# PCB_Telemetria_2020.net
KiCad netlist of a schematic drawn in EAGLE
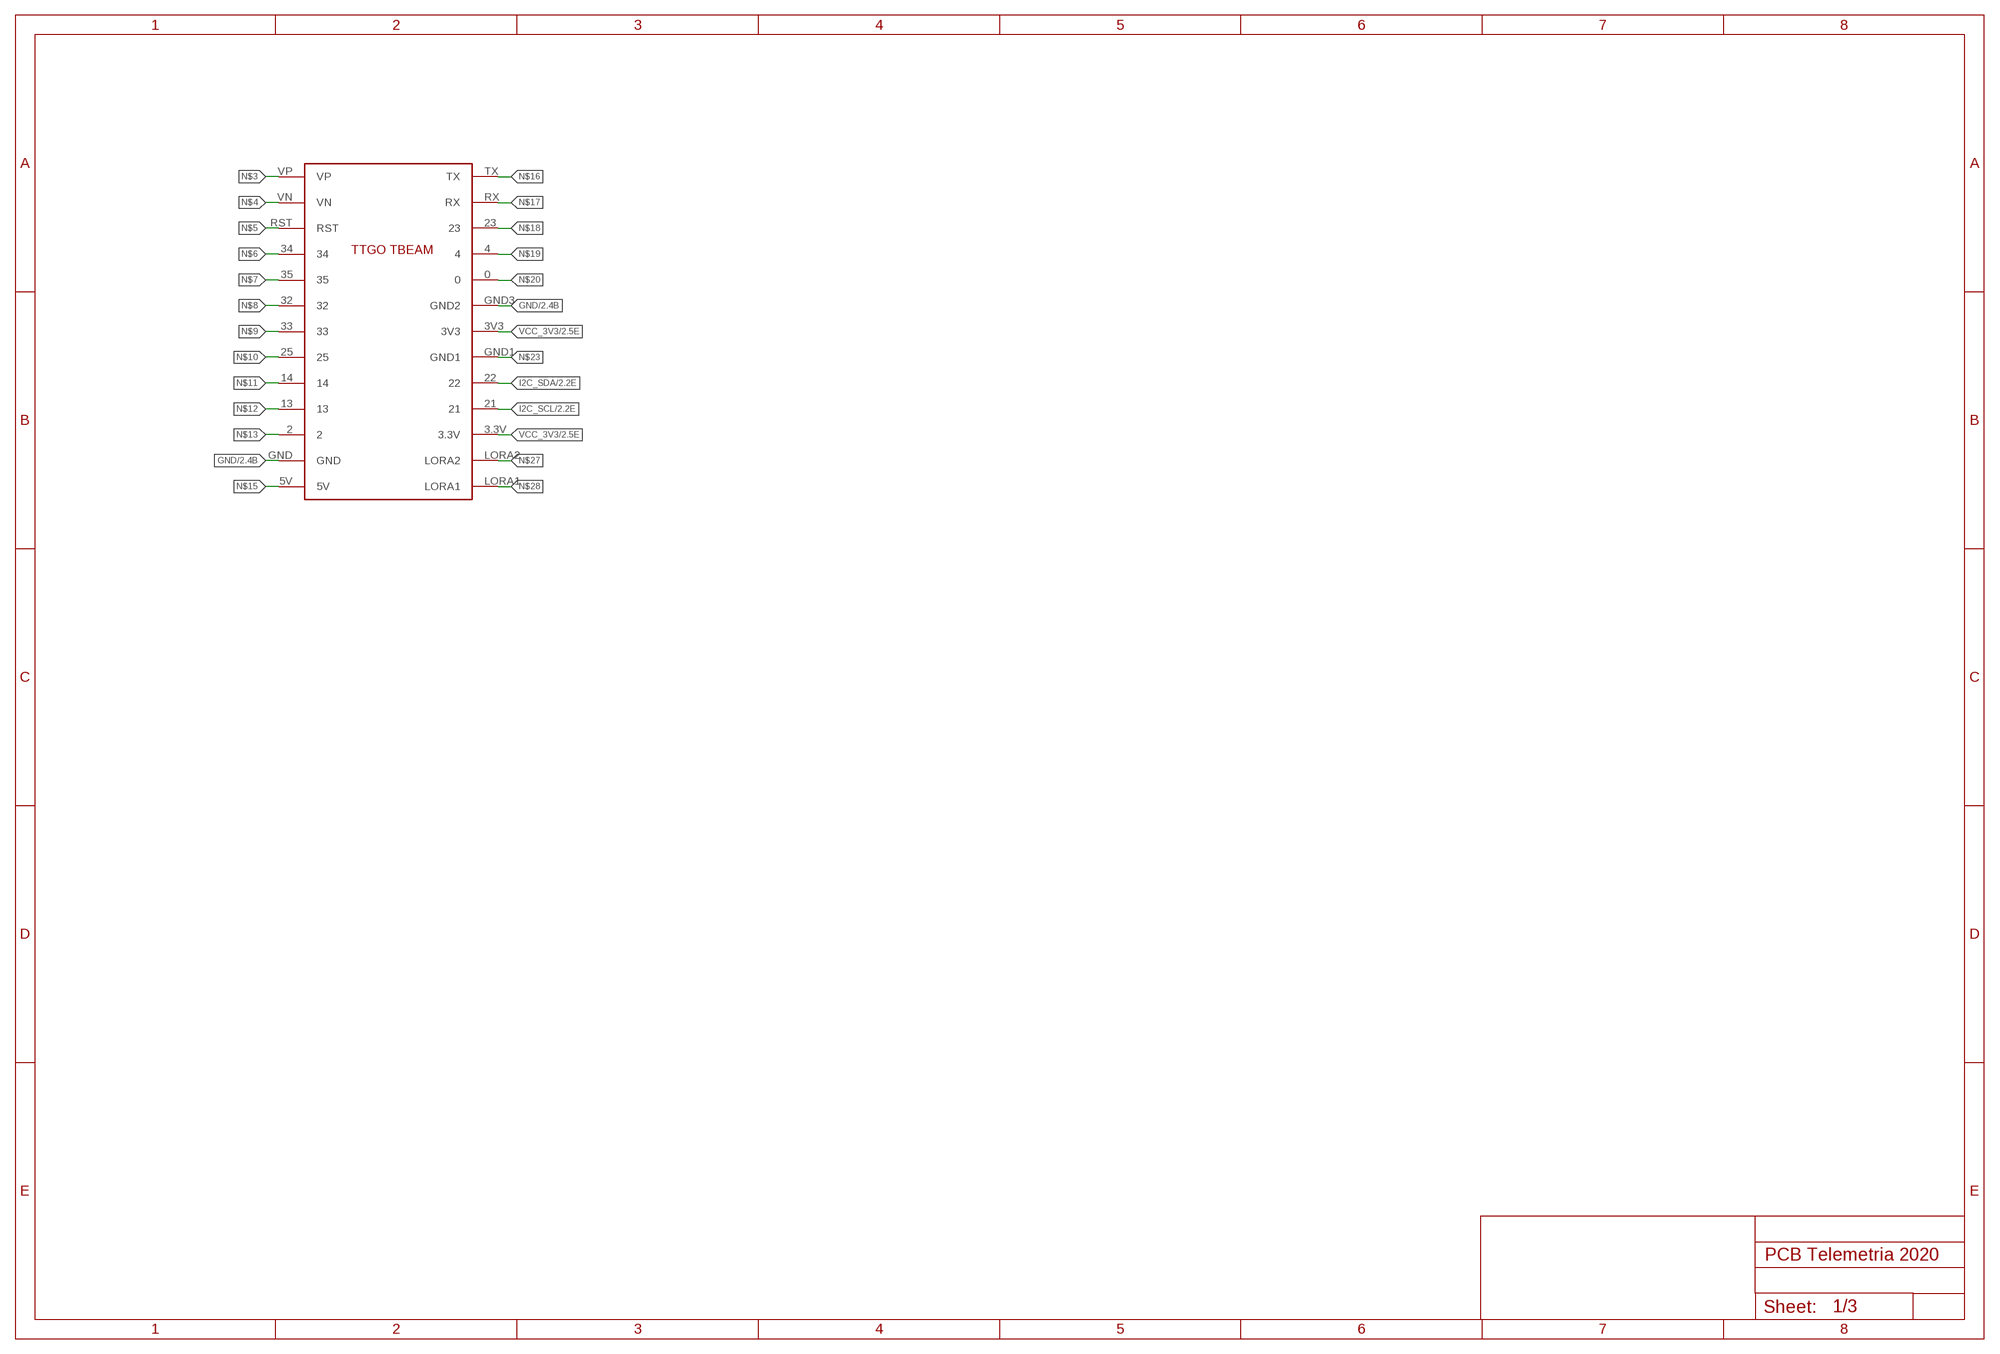
[diagram p0: schematic, sheet 1]
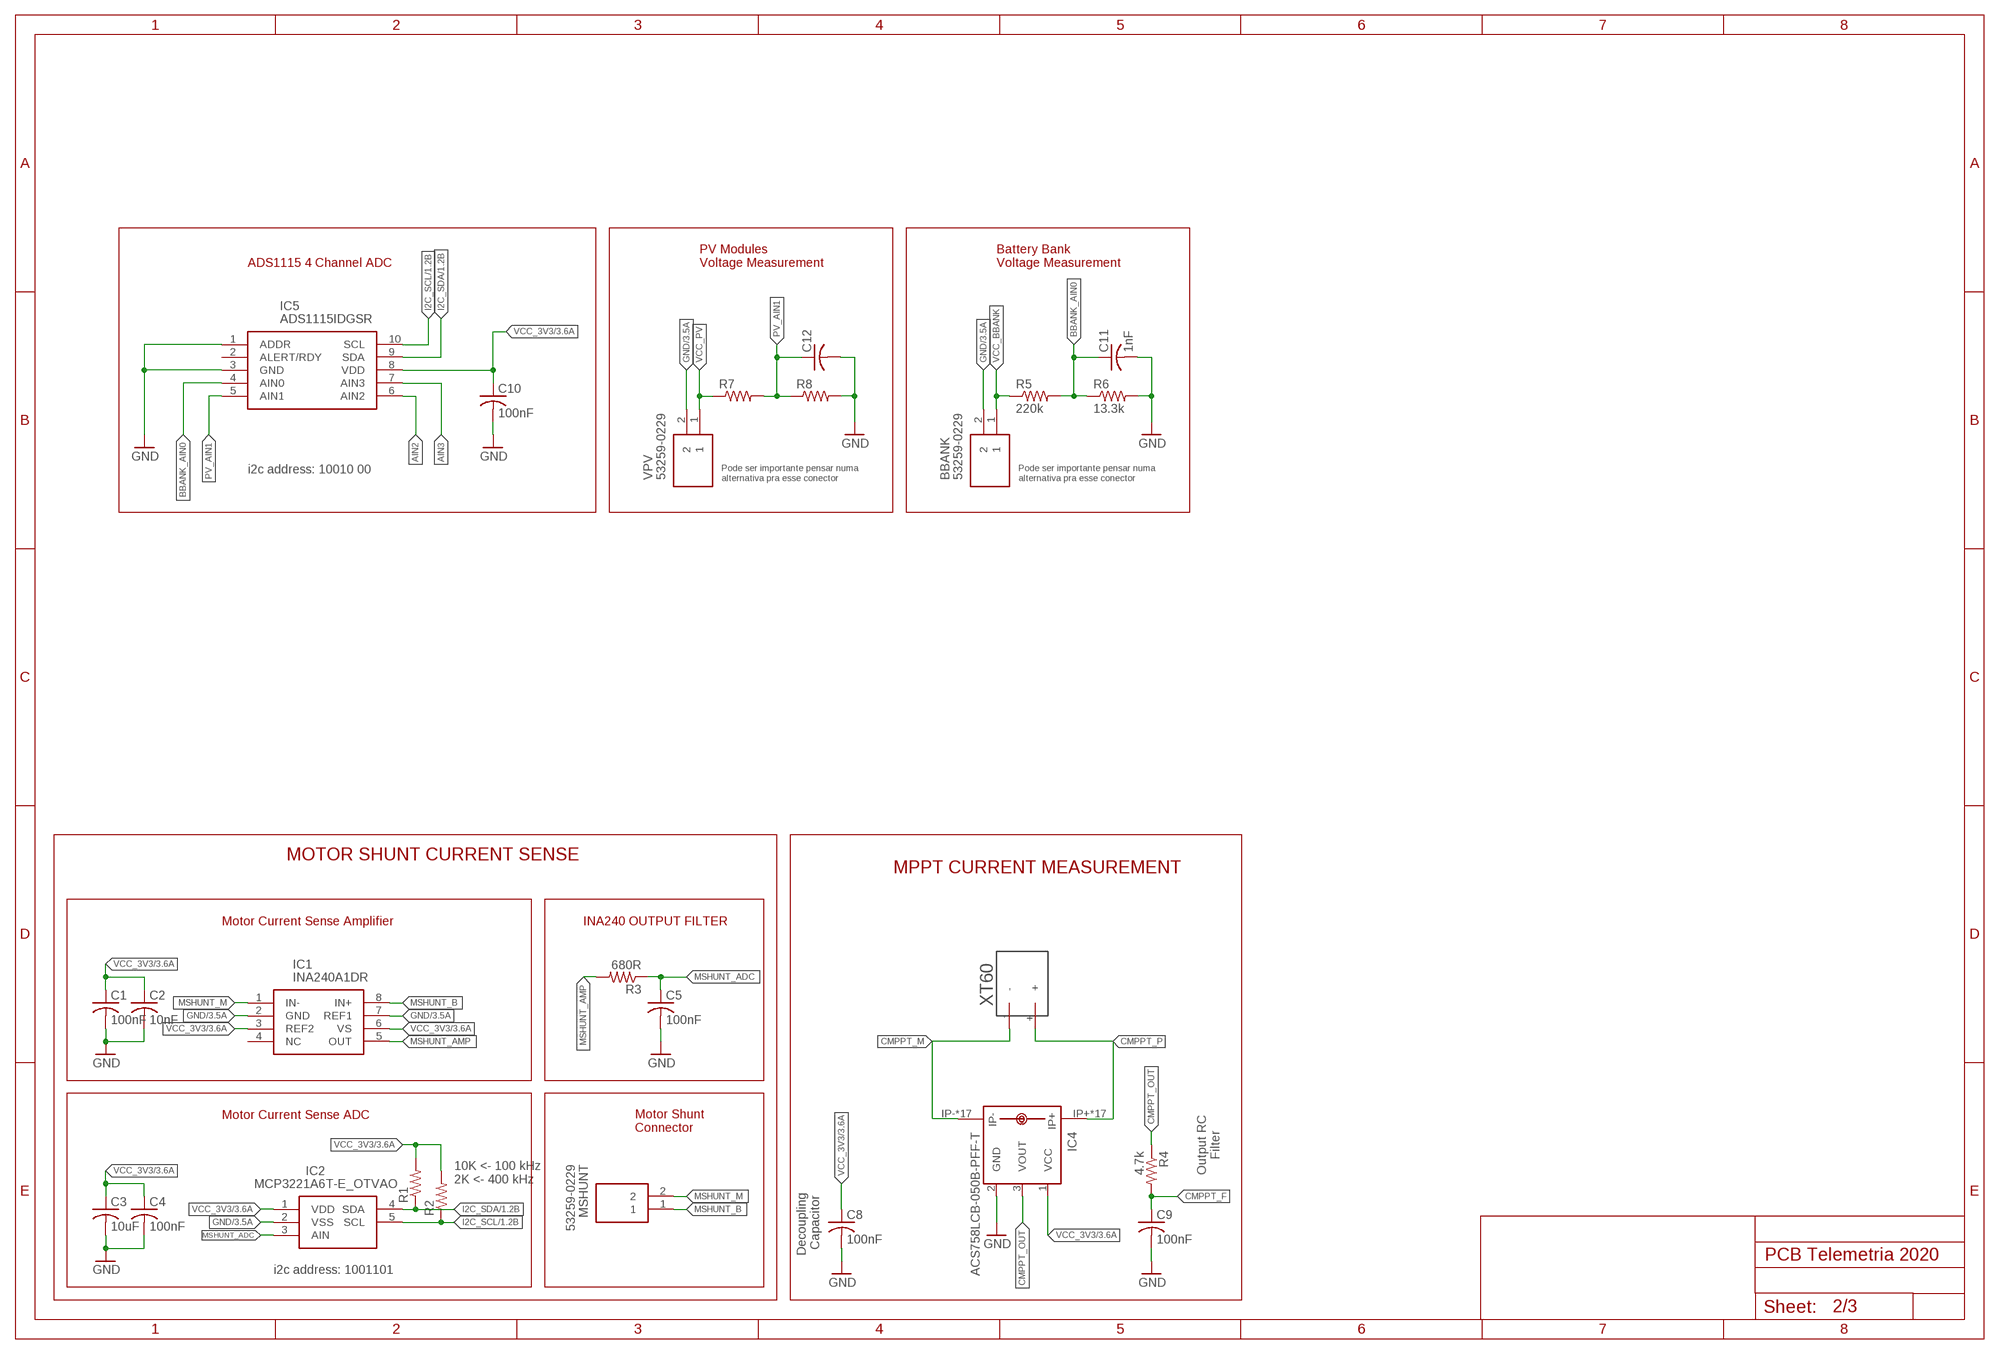
[diagram p1: schematic, sheet 2]
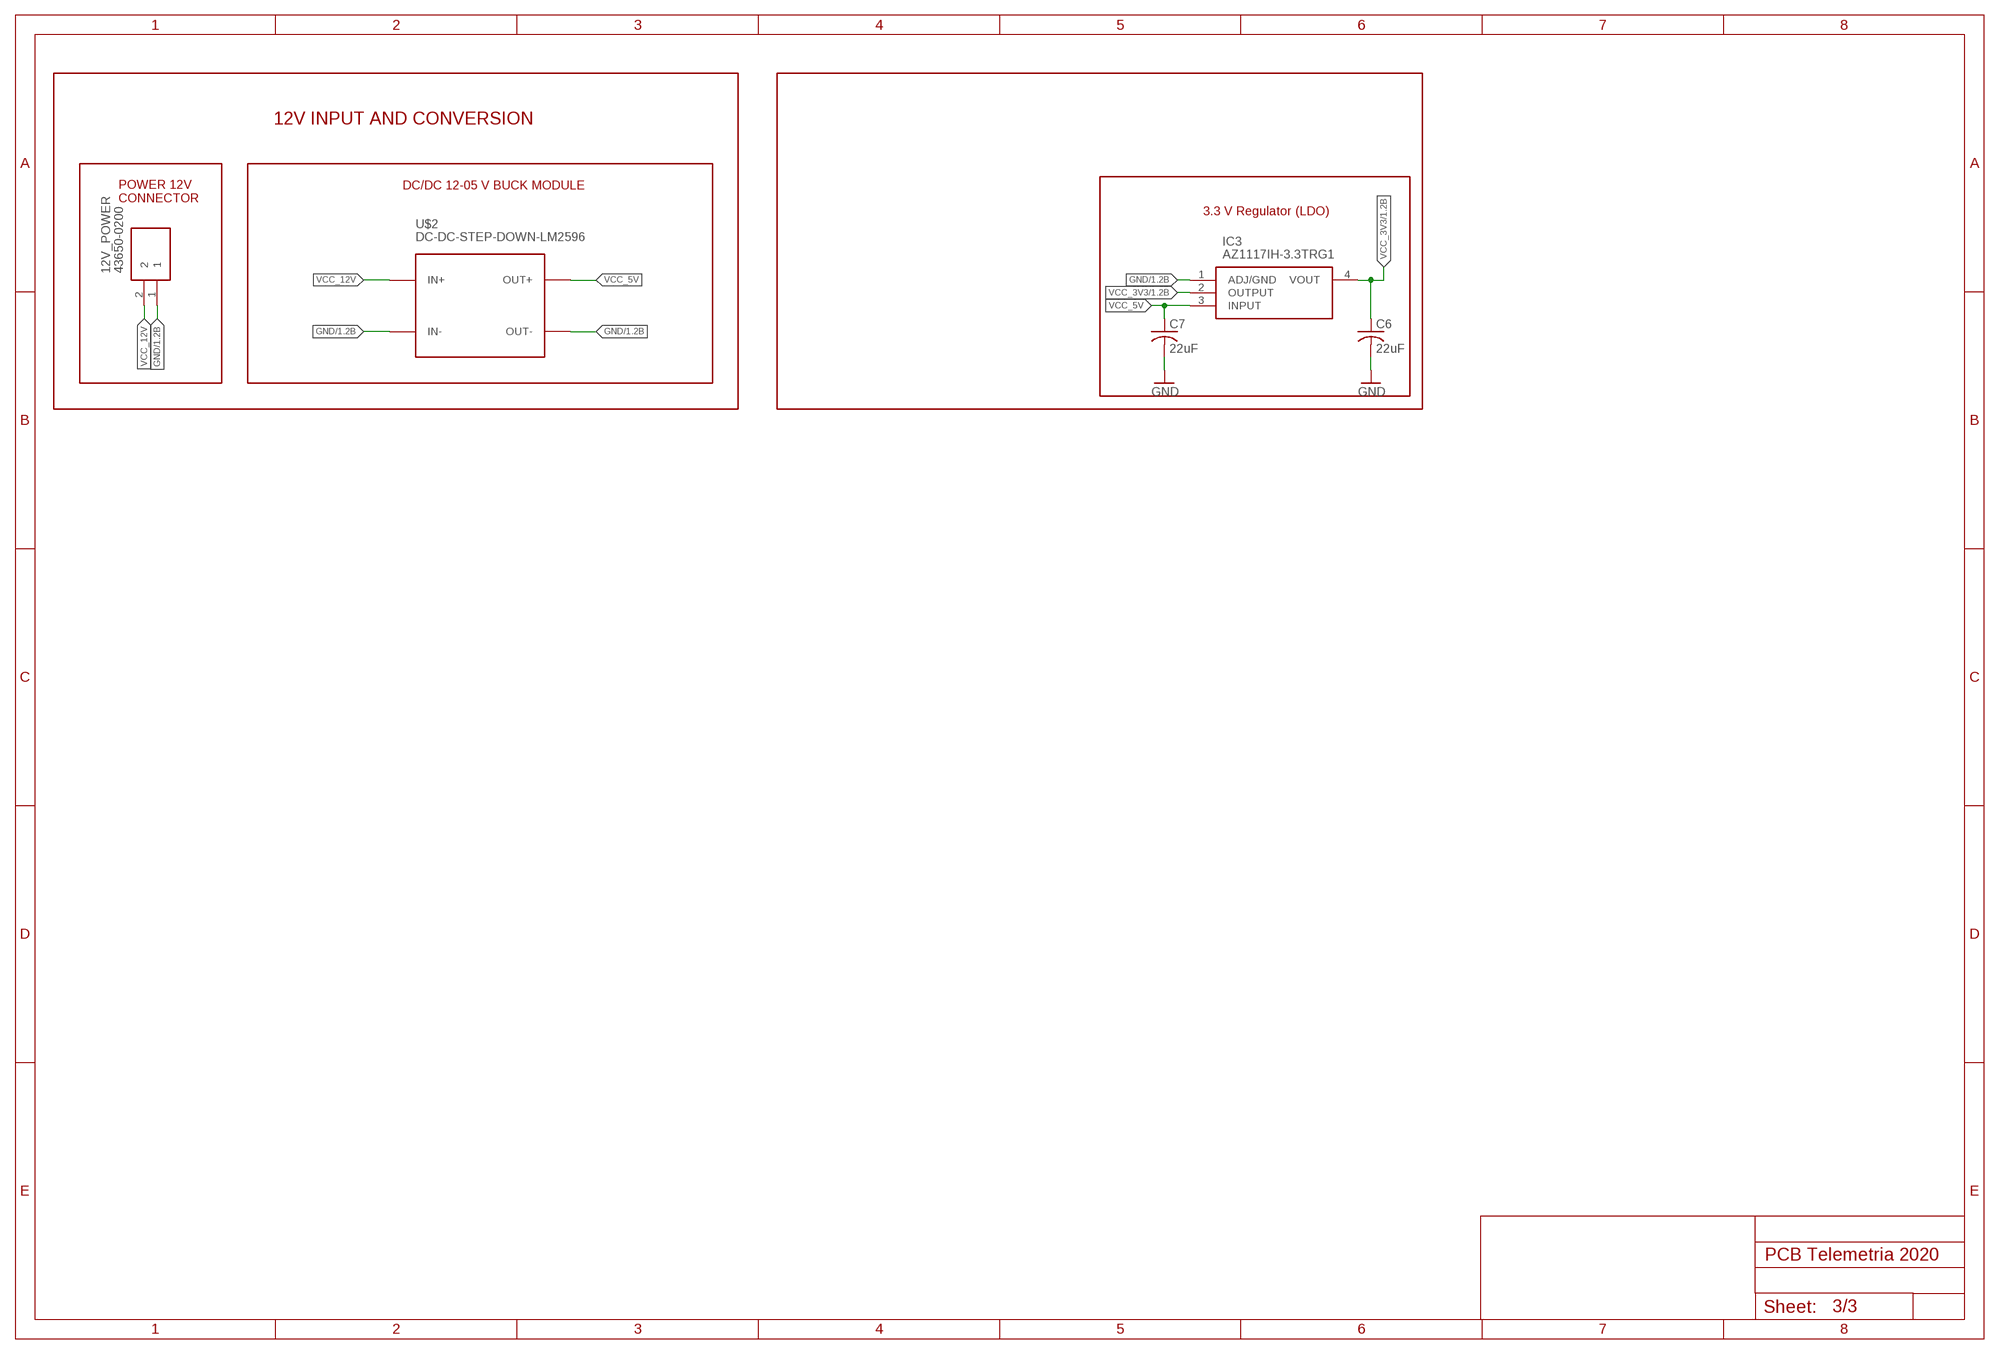
[diagram p2: schematic, sheet 3]

(export (version "E")
  (design (tool "Eeschema 10.0.6"))
  (components
    (comp (ref "U$1")
      (value "TTGOBEAM")
      (footprint "eagle-import:TTGOBEAM")
      (libsource (lib "eagle-import") (part "TTGOBEAM"))
    )
    (comp (ref "12V_POWER")
      (value "43650-0200")
      (footprint "eagle-import:43650-0200")
      (fields (field (name "MOUSER_PART_NUMBER") "538-43650-0200"))
      (libsource (lib "eagle-import") (part "43650-0200"))
    )
    (comp (ref "C6")
      (value "22uF")
      (footprint "eagle-import:C0805")
      (libsource (lib "eagle-import") (part "C-USC0805"))
    )
    (comp (ref "C7")
      (value "22uF")
      (footprint "eagle-import:C0805")
      (libsource (lib "eagle-import") (part "C-USC0805"))
    )
    (comp (ref "IC3")
      (value "AZ1117IH-3.3TRG1")
      (footprint "eagle-import:SOT230P700X170-4N")
      (fields (field (name "MOUSER_PART_NUMBER") "621-AZ1117IH-3.3TRG1"))
      (libsource (lib "eagle-import") (part "AZ1117IH-3.3TRG1"))
    )
    (comp (ref "U$2")
      (value "DC-DC-STEP-DOWN-LM2596")
      (footprint "eagle-import:DC-DC-STEP-DOWN-LM2596")
      (libsource (lib "eagle-import") (part "DC-DC-STEP-DOWN-LM2596"))
    )
    (comp (ref "BBANK")
      (value "53259-0229")
      (footprint "eagle-import:0532590229")
      (fields (field (name "MOUSER_PART_NUMBER") "538-53259-0229"))
      (libsource (lib "eagle-import") (part "53259-0229"))
    )
    (comp (ref "C1")
      (value "100nF")
      (footprint "eagle-import:C0805")
      (libsource (lib "eagle-import") (part "C-USC0805"))
    )
    (comp (ref "C2")
      (value "10nF")
      (footprint "eagle-import:C0805")
      (libsource (lib "eagle-import") (part "C-USC0805"))
    )
    (comp (ref "C3")
      (value "10uF")
      (footprint "eagle-import:C0805")
      (libsource (lib "eagle-import") (part "C-USC0805"))
    )
    (comp (ref "C4")
      (value "100nF")
      (footprint "eagle-import:C0805")
      (libsource (lib "eagle-import") (part "C-USC0805"))
    )
    (comp (ref "C5")
      (value "100nF")
      (footprint "eagle-import:C0805")
      (libsource (lib "eagle-import") (part "C-USC0805"))
    )
    (comp (ref "C8")
      (value "100nF")
      (footprint "eagle-import:C0805")
      (libsource (lib "eagle-import") (part "C-USC0805"))
    )
    (comp (ref "C9")
      (value "100nF")
      (footprint "eagle-import:C0805")
      (libsource (lib "eagle-import") (part "C-USC0805"))
    )
    (comp (ref "C10")
      (value "100nF")
      (footprint "eagle-import:C0805")
      (libsource (lib "eagle-import") (part "C-USC0805"))
    )
    (comp (ref "C11")
      (value "1nF")
      (footprint "eagle-import:C0805")
      (libsource (lib "eagle-import") (part "C-USC0805"))
    )
    (comp (ref "C12")
      (value "C-USC0805")
      (footprint "eagle-import:C0805")
      (libsource (lib "eagle-import") (part "C-USC0805"))
    )
    (comp (ref "IC1")
      (value "INA240A1DR")
      (footprint "eagle-import:SOIC127P600X175-8N")
      (fields (field (name "MOUSER_PART_NUMBER") "595-INA240A1DR"))
      (libsource (lib "eagle-import") (part "INA240A1DR"))
    )
    (comp (ref "IC2")
      (value "MCP3221A6T-E_OTVAO")
      (footprint "eagle-import:SOT95P280X145-5N")
      (fields
        (field (name "MANUFACTURER_PART_NUMBER") "MCP3221A6T-E/OTVAO")
        (field (name "MOUSER_PART_NUMBER") "579-MCP3221A6TEOTVAO")
      )
      (libsource (lib "eagle-import") (part "MCP3221A6T-E_OTVAO"))
    )
    (comp (ref "IC4")
      (value "ACS758LCB-050B-PFF-T")
      (footprint "eagle-import:CB-PFF")
      (libsource (lib "eagle-import") (part "ACS758LCB-050B-PFF-T"))
    )
    (comp (ref "IC5")
      (value "ADS1115IDGSR")
      (footprint "eagle-import:SOP50P490X110-10N")
      (fields (field (name "MOUSER_PART_NUMBER") "595-ADS1115IDGSR"))
      (libsource (lib "eagle-import") (part "ADS1115IDGSR"))
    )
    (comp (ref "MSHUNT")
      (value "53259-0229")
      (footprint "eagle-import:0532590229")
      (fields (field (name "MOUSER_PART_NUMBER") "538-53259-0229"))
      (libsource (lib "eagle-import") (part "53259-0229"))
    )
    (comp (ref "R1")
      (value "R-US_R0805")
      (footprint "eagle-import:R0805")
      (libsource (lib "eagle-import") (part "R-US_R0805"))
    )
    (comp (ref "R2")
      (value "R-US_R0805")
      (footprint "eagle-import:R0805")
      (libsource (lib "eagle-import") (part "R-US_R0805"))
    )
    (comp (ref "R3")
      (value "680R")
      (footprint "eagle-import:R0805")
      (libsource (lib "eagle-import") (part "R-US_R0805"))
    )
    (comp (ref "R4")
      (value "4.7k")
      (footprint "eagle-import:R0805")
      (libsource (lib "eagle-import") (part "R-US_R0805"))
    )
    (comp (ref "R5")
      (value "220k")
      (footprint "eagle-import:R0805")
      (libsource (lib "eagle-import") (part "R-US_R0805"))
    )
    (comp (ref "R6")
      (value "13.3k")
      (footprint "eagle-import:R0805")
      (libsource (lib "eagle-import") (part "R-US_R0805"))
    )
    (comp (ref "R7")
      (value "R-US_R0805")
      (footprint "eagle-import:R0805")
      (libsource (lib "eagle-import") (part "R-US_R0805"))
    )
    (comp (ref "R8")
      (value "R-US_R0805")
      (footprint "eagle-import:R0805")
      (libsource (lib "eagle-import") (part "R-US_R0805"))
    )
    (comp (ref "U$3")
      (value "XT60")
      (footprint "eagle-import:XT60")
      (libsource (lib "eagle-import") (part "XT60"))
    )
    (comp (ref "VPV")
      (value "53259-0229")
      (footprint "eagle-import:0532590229")
      (fields (field (name "MOUSER_PART_NUMBER") "538-53259-0229"))
      (libsource (lib "eagle-import") (part "53259-0229"))
    )
  )
  (nets
    (net (code "1") (name "AIN2") (class "Default")
      (node (ref "IC5") (pin "6") (pinfunction "AIN2_6") (pintype "bidirectional"))
    )
    (net (code "2") (name "AIN3") (class "Default")
      (node (ref "IC5") (pin "7") (pinfunction "AIN3_7") (pintype "bidirectional"))
    )
    (net (code "3") (name "BBANK_AIN0") (class "Default")
      (node (ref "C11") (pin "1") (pinfunction "1_1") (pintype "passive"))
      (node (ref "IC5") (pin "4") (pinfunction "AIN0_4") (pintype "bidirectional"))
      (node (ref "R5") (pin "2") (pinfunction "2_2") (pintype "passive"))
      (node (ref "R6") (pin "1") (pinfunction "1_1") (pintype "passive"))
    )
    (net (code "4") (name "CMPPT_F") (class "Default")
      (node (ref "C9") (pin "1") (pinfunction "1_1") (pintype "passive"))
      (node (ref "R4") (pin "2") (pinfunction "2_2") (pintype "passive"))
    )
    (net (code "5") (name "CMPPT_M") (class "Default")
      (node (ref "IC4") (pin "IP-") (pinfunction "IP-_IP-") (pintype "passive"))
      (node (ref "IC4") (pin "IP-@10") (pinfunction "IP-_IP-@10") (pintype "passive"))
      (node (ref "IC4") (pin "IP-@11") (pinfunction "IP-_IP-@11") (pintype "passive"))
      (node (ref "IC4") (pin "IP-@12") (pinfunction "IP-_IP-@12") (pintype "passive"))
      (node (ref "IC4") (pin "IP-@13") (pinfunction "IP-_IP-@13") (pintype "passive"))
      (node (ref "IC4") (pin "IP-@14") (pinfunction "IP-_IP-@14") (pintype "passive"))
      (node (ref "IC4") (pin "IP-@15") (pinfunction "IP-_IP-@15") (pintype "passive"))
      (node (ref "IC4") (pin "IP-@16") (pinfunction "IP-_IP-@16") (pintype "passive"))
      (node (ref "IC4") (pin "IP-@17") (pinfunction "IP-_IP-@17") (pintype "passive"))
      (node (ref "IC4") (pin "IP-@2") (pinfunction "IP-_IP-@2") (pintype "passive"))
      (node (ref "IC4") (pin "IP-@3") (pinfunction "IP-_IP-@3") (pintype "passive"))
      (node (ref "IC4") (pin "IP-@4") (pinfunction "IP-_IP-@4") (pintype "passive"))
      (node (ref "IC4") (pin "IP-@5") (pinfunction "IP-_IP-@5") (pintype "passive"))
      (node (ref "IC4") (pin "IP-@6") (pinfunction "IP-_IP-@6") (pintype "passive"))
      (node (ref "IC4") (pin "IP-@7") (pinfunction "IP-_IP-@7") (pintype "passive"))
      (node (ref "IC4") (pin "IP-@8") (pinfunction "IP-_IP-@8") (pintype "passive"))
      (node (ref "IC4") (pin "IP-@9") (pinfunction "IP-_IP-@9") (pintype "passive"))
      (node (ref "U$3") (pin "-") (pinfunction "-_-") (pintype "bidirectional"))
    )
    (net (code "6") (name "CMPPT_OUT") (class "Default")
      (node (ref "IC4") (pin "3") (pinfunction "VOUT_3") (pintype "output"))
      (node (ref "R4") (pin "1") (pinfunction "1_1") (pintype "passive"))
    )
    (net (code "7") (name "CMPPT_P") (class "Default")
      (node (ref "IC4") (pin "IP+") (pinfunction "IP+_IP+") (pintype "passive"))
      (node (ref "IC4") (pin "IP+@10") (pinfunction "IP+_IP+@10") (pintype "passive"))
      (node (ref "IC4") (pin "IP+@11") (pinfunction "IP+_IP+@11") (pintype "passive"))
      (node (ref "IC4") (pin "IP+@12") (pinfunction "IP+_IP+@12") (pintype "passive"))
      (node (ref "IC4") (pin "IP+@13") (pinfunction "IP+_IP+@13") (pintype "passive"))
      (node (ref "IC4") (pin "IP+@14") (pinfunction "IP+_IP+@14") (pintype "passive"))
      (node (ref "IC4") (pin "IP+@15") (pinfunction "IP+_IP+@15") (pintype "passive"))
      (node (ref "IC4") (pin "IP+@16") (pinfunction "IP+_IP+@16") (pintype "passive"))
      (node (ref "IC4") (pin "IP+@17") (pinfunction "IP+_IP+@17") (pintype "passive"))
      (node (ref "IC4") (pin "IP+@2") (pinfunction "IP+_IP+@2") (pintype "passive"))
      (node (ref "IC4") (pin "IP+@3") (pinfunction "IP+_IP+@3") (pintype "passive"))
      (node (ref "IC4") (pin "IP+@4") (pinfunction "IP+_IP+@4") (pintype "passive"))
      (node (ref "IC4") (pin "IP+@5") (pinfunction "IP+_IP+@5") (pintype "passive"))
      (node (ref "IC4") (pin "IP+@6") (pinfunction "IP+_IP+@6") (pintype "passive"))
      (node (ref "IC4") (pin "IP+@7") (pinfunction "IP+_IP+@7") (pintype "passive"))
      (node (ref "IC4") (pin "IP+@8") (pinfunction "IP+_IP+@8") (pintype "passive"))
      (node (ref "IC4") (pin "IP+@9") (pinfunction "IP+_IP+@9") (pintype "passive"))
      (node (ref "U$3") (pin "+") (pinfunction "+_+") (pintype "bidirectional"))
    )
    (net (code "8") (name "GND") (class "Default")
      (node (ref "12V_POWER") (pin "1") (pinfunction "1_1") (pintype "bidirectional"))
      (node (ref "BBANK") (pin "2") (pinfunction "2_2") (pintype "bidirectional"))
      (node (ref "C1") (pin "2") (pinfunction "2_2") (pintype "passive"))
      (node (ref "C10") (pin "2") (pinfunction "2_2") (pintype "passive"))
      (node (ref "C11") (pin "2") (pinfunction "2_2") (pintype "passive"))
      (node (ref "C12") (pin "2") (pinfunction "2_2") (pintype "passive"))
      (node (ref "C2") (pin "2") (pinfunction "2_2") (pintype "passive"))
      (node (ref "C3") (pin "2") (pinfunction "2_2") (pintype "passive"))
      (node (ref "C4") (pin "2") (pinfunction "2_2") (pintype "passive"))
      (node (ref "C5") (pin "2") (pinfunction "2_2") (pintype "passive"))
      (node (ref "C6") (pin "2") (pinfunction "2_2") (pintype "passive"))
      (node (ref "C7") (pin "2") (pinfunction "2_2") (pintype "passive"))
      (node (ref "C8") (pin "2") (pinfunction "2_2") (pintype "passive"))
      (node (ref "C9") (pin "2") (pinfunction "2_2") (pintype "passive"))
      (node (ref "IC1") (pin "2") (pinfunction "GND_2") (pintype "bidirectional"))
      (node (ref "IC1") (pin "7") (pinfunction "REF1_7") (pintype "bidirectional"))
      (node (ref "IC2") (pin "2") (pinfunction "VSS_2") (pintype "bidirectional"))
      (node (ref "IC3") (pin "1") (pinfunction "ADJ/GND_1") (pintype "bidirectional"))
      (node (ref "IC4") (pin "2") (pinfunction "GND_2") (pintype "power_in"))
      (node (ref "IC5") (pin "1") (pinfunction "ADDR_1") (pintype "bidirectional"))
      (node (ref "IC5") (pin "3") (pinfunction "GND_3") (pintype "bidirectional"))
      (node (ref "R6") (pin "2") (pinfunction "2_2") (pintype "passive"))
      (node (ref "R8") (pin "2") (pinfunction "2_2") (pintype "passive"))
      (node (ref "U$1") (pin "GND") (pinfunction "GND_GND") (pintype "bidirectional"))
      (node (ref "U$1") (pin "GND3") (pinfunction "GND2_GND3") (pintype "bidirectional"))
      (node (ref "U$2") (pin "IN-") (pinfunction "IN-_IN-") (pintype "bidirectional"))
      (node (ref "U$2") (pin "OUT-") (pinfunction "OUT-_OUT-") (pintype "bidirectional"))
      (node (ref "VPV") (pin "2") (pinfunction "2_2") (pintype "bidirectional"))
    )
    (net (code "9") (name "I2C_SCL") (class "Default")
      (node (ref "IC2") (pin "5") (pinfunction "SCL_5") (pintype "bidirectional"))
      (node (ref "IC5") (pin "10") (pinfunction "SCL_10") (pintype "bidirectional"))
      (node (ref "R2") (pin "1") (pinfunction "1_1") (pintype "passive"))
      (node (ref "U$1") (pin "21") (pinfunction "21_21") (pintype "bidirectional"))
    )
    (net (code "10") (name "I2C_SDA") (class "Default")
      (node (ref "IC2") (pin "4") (pinfunction "SDA_4") (pintype "bidirectional"))
      (node (ref "IC5") (pin "9") (pinfunction "SDA_9") (pintype "bidirectional"))
      (node (ref "R1") (pin "1") (pinfunction "1_1") (pintype "passive"))
      (node (ref "U$1") (pin "22") (pinfunction "22_22") (pintype "bidirectional"))
    )
    (net (code "11") (name "MSHUNT_ADC") (class "Default")
      (node (ref "C5") (pin "1") (pinfunction "1_1") (pintype "passive"))
      (node (ref "IC2") (pin "3") (pinfunction "AIN_3") (pintype "bidirectional"))
      (node (ref "R3") (pin "1") (pinfunction "1_1") (pintype "passive"))
    )
    (net (code "12") (name "MSHUNT_AMP") (class "Default")
      (node (ref "IC1") (pin "5") (pinfunction "OUT_5") (pintype "bidirectional"))
      (node (ref "R3") (pin "2") (pinfunction "2_2") (pintype "passive"))
    )
    (net (code "13") (name "MSHUNT_B") (class "Default")
      (node (ref "IC1") (pin "8") (pinfunction "IN+_8") (pintype "bidirectional"))
      (node (ref "MSHUNT") (pin "1") (pinfunction "1_1") (pintype "bidirectional"))
    )
    (net (code "14") (name "MSHUNT_M") (class "Default")
      (node (ref "IC1") (pin "1") (pinfunction "IN-_1") (pintype "bidirectional"))
      (node (ref "MSHUNT") (pin "2") (pinfunction "2_2") (pintype "bidirectional"))
    )
    (net (code "15") (name "N$3") (class "Default")
      (node (ref "U$1") (pin "VP") (pinfunction "VP_VP") (pintype "bidirectional"))
    )
    (net (code "16") (name "N$4") (class "Default")
      (node (ref "U$1") (pin "VN") (pinfunction "VN_VN") (pintype "bidirectional"))
    )
    (net (code "17") (name "N$5") (class "Default")
      (node (ref "U$1") (pin "RST") (pinfunction "RST_RST") (pintype "bidirectional"))
    )
    (net (code "18") (name "N$6") (class "Default")
      (node (ref "U$1") (pin "34") (pinfunction "34_34") (pintype "bidirectional"))
    )
    (net (code "19") (name "N$7") (class "Default")
      (node (ref "U$1") (pin "35") (pinfunction "35_35") (pintype "bidirectional"))
    )
    (net (code "20") (name "N$8") (class "Default")
      (node (ref "U$1") (pin "32") (pinfunction "32_32") (pintype "bidirectional"))
    )
    (net (code "21") (name "N$9") (class "Default")
      (node (ref "U$1") (pin "33") (pinfunction "33_33") (pintype "bidirectional"))
    )
    (net (code "22") (name "N$10") (class "Default")
      (node (ref "U$1") (pin "25") (pinfunction "25_25") (pintype "bidirectional"))
    )
    (net (code "23") (name "N$11") (class "Default")
      (node (ref "U$1") (pin "14") (pinfunction "14_14") (pintype "bidirectional"))
    )
    (net (code "24") (name "N$12") (class "Default")
      (node (ref "U$1") (pin "13") (pinfunction "13_13") (pintype "bidirectional"))
    )
    (net (code "25") (name "N$13") (class "Default")
      (node (ref "U$1") (pin "2") (pinfunction "2_2") (pintype "bidirectional"))
    )
    (net (code "26") (name "N$15") (class "Default")
      (node (ref "U$1") (pin "5V") (pinfunction "5V_5V") (pintype "bidirectional"))
    )
    (net (code "27") (name "N$16") (class "Default")
      (node (ref "U$1") (pin "TX") (pinfunction "TX_TX") (pintype "bidirectional"))
    )
    (net (code "28") (name "N$17") (class "Default")
      (node (ref "U$1") (pin "RX") (pinfunction "RX_RX") (pintype "bidirectional"))
    )
    (net (code "29") (name "N$18") (class "Default")
      (node (ref "U$1") (pin "23") (pinfunction "23_23") (pintype "bidirectional"))
    )
    (net (code "30") (name "N$19") (class "Default")
      (node (ref "U$1") (pin "4") (pinfunction "4_4") (pintype "bidirectional"))
    )
    (net (code "31") (name "N$20") (class "Default")
      (node (ref "U$1") (pin "0") (pinfunction "0_0") (pintype "bidirectional"))
    )
    (net (code "32") (name "N$23") (class "Default")
      (node (ref "U$1") (pin "GND1") (pinfunction "GND1_GND1") (pintype "bidirectional"))
    )
    (net (code "33") (name "N$27") (class "Default")
      (node (ref "U$1") (pin "LORA2") (pinfunction "LORA2_LORA2") (pintype "bidirectional"))
    )
    (net (code "34") (name "N$28") (class "Default")
      (node (ref "U$1") (pin "LORA1") (pinfunction "LORA1_LORA1") (pintype "bidirectional"))
    )
    (net (code "35") (name "PV_AIN1") (class "Default")
      (node (ref "C12") (pin "1") (pinfunction "1_1") (pintype "passive"))
      (node (ref "IC5") (pin "5") (pinfunction "AIN1_5") (pintype "bidirectional"))
      (node (ref "R7") (pin "2") (pinfunction "2_2") (pintype "passive"))
      (node (ref "R8") (pin "1") (pinfunction "1_1") (pintype "passive"))
    )
    (net (code "36") (name "VCC_3V3") (class "Default")
      (node (ref "C1") (pin "1") (pinfunction "1_1") (pintype "passive"))
      (node (ref "C10") (pin "1") (pinfunction "1_1") (pintype "passive"))
      (node (ref "C2") (pin "1") (pinfunction "1_1") (pintype "passive"))
      (node (ref "C3") (pin "1") (pinfunction "1_1") (pintype "passive"))
      (node (ref "C4") (pin "1") (pinfunction "1_1") (pintype "passive"))
      (node (ref "C6") (pin "1") (pinfunction "1_1") (pintype "passive"))
      (node (ref "C8") (pin "1") (pinfunction "1_1") (pintype "passive"))
      (node (ref "IC1") (pin "3") (pinfunction "REF2_3") (pintype "bidirectional"))
      (node (ref "IC1") (pin "6") (pinfunction "VS_6") (pintype "bidirectional"))
      (node (ref "IC2") (pin "1") (pinfunction "VDD_1") (pintype "bidirectional"))
      (node (ref "IC3") (pin "2") (pinfunction "OUTPUT_2") (pintype "bidirectional"))
      (node (ref "IC3") (pin "4") (pinfunction "VOUT_4") (pintype "bidirectional"))
      (node (ref "IC4") (pin "1") (pinfunction "VCC_1") (pintype "power_in"))
      (node (ref "IC5") (pin "8") (pinfunction "VDD_8") (pintype "bidirectional"))
      (node (ref "R1") (pin "2") (pinfunction "2_2") (pintype "passive"))
      (node (ref "R2") (pin "2") (pinfunction "2_2") (pintype "passive"))
      (node (ref "U$1") (pin "3.3V") (pinfunction "3.3V_3.3V") (pintype "bidirectional"))
      (node (ref "U$1") (pin "3V3") (pinfunction "3V3_3V3") (pintype "bidirectional"))
    )
    (net (code "37") (name "VCC_5V") (class "Default")
      (node (ref "C7") (pin "1") (pinfunction "1_1") (pintype "passive"))
      (node (ref "IC3") (pin "3") (pinfunction "INPUT_3") (pintype "bidirectional"))
      (node (ref "U$2") (pin "OUT+") (pinfunction "OUT+_OUT+") (pintype "bidirectional"))
    )
    (net (code "38") (name "VCC_12V") (class "Default")
      (node (ref "12V_POWER") (pin "2") (pinfunction "2_2") (pintype "bidirectional"))
      (node (ref "U$2") (pin "IN+") (pinfunction "IN+_IN+") (pintype "bidirectional"))
    )
    (net (code "39") (name "VCC_BBANK") (class "Default")
      (node (ref "BBANK") (pin "1") (pinfunction "1_1") (pintype "bidirectional"))
      (node (ref "R5") (pin "1") (pinfunction "1_1") (pintype "passive"))
    )
    (net (code "40") (name "VCC_PV") (class "Default")
      (node (ref "R7") (pin "1") (pinfunction "1_1") (pintype "passive"))
      (node (ref "VPV") (pin "1") (pinfunction "1_1") (pintype "bidirectional"))
    )
    (net (code "41") (name "unconnected-(IC1-NC-Pad4)") (class "Default")
      (node (ref "IC1") (pin "4") (pinfunction "NC_4") (pintype "no_connect"))
    )
    (net (code "42") (name "unconnected-(IC5-ALERT{slash}RDY-Pad2)") (class "Default")
      (node (ref "IC5") (pin "2") (pinfunction "ALERT/RDY_2") (pintype "bidirectional"))
    )
  )
)
